# 4-PT100-B.net
KiCad netlist of a schematic drawn in EAGLE
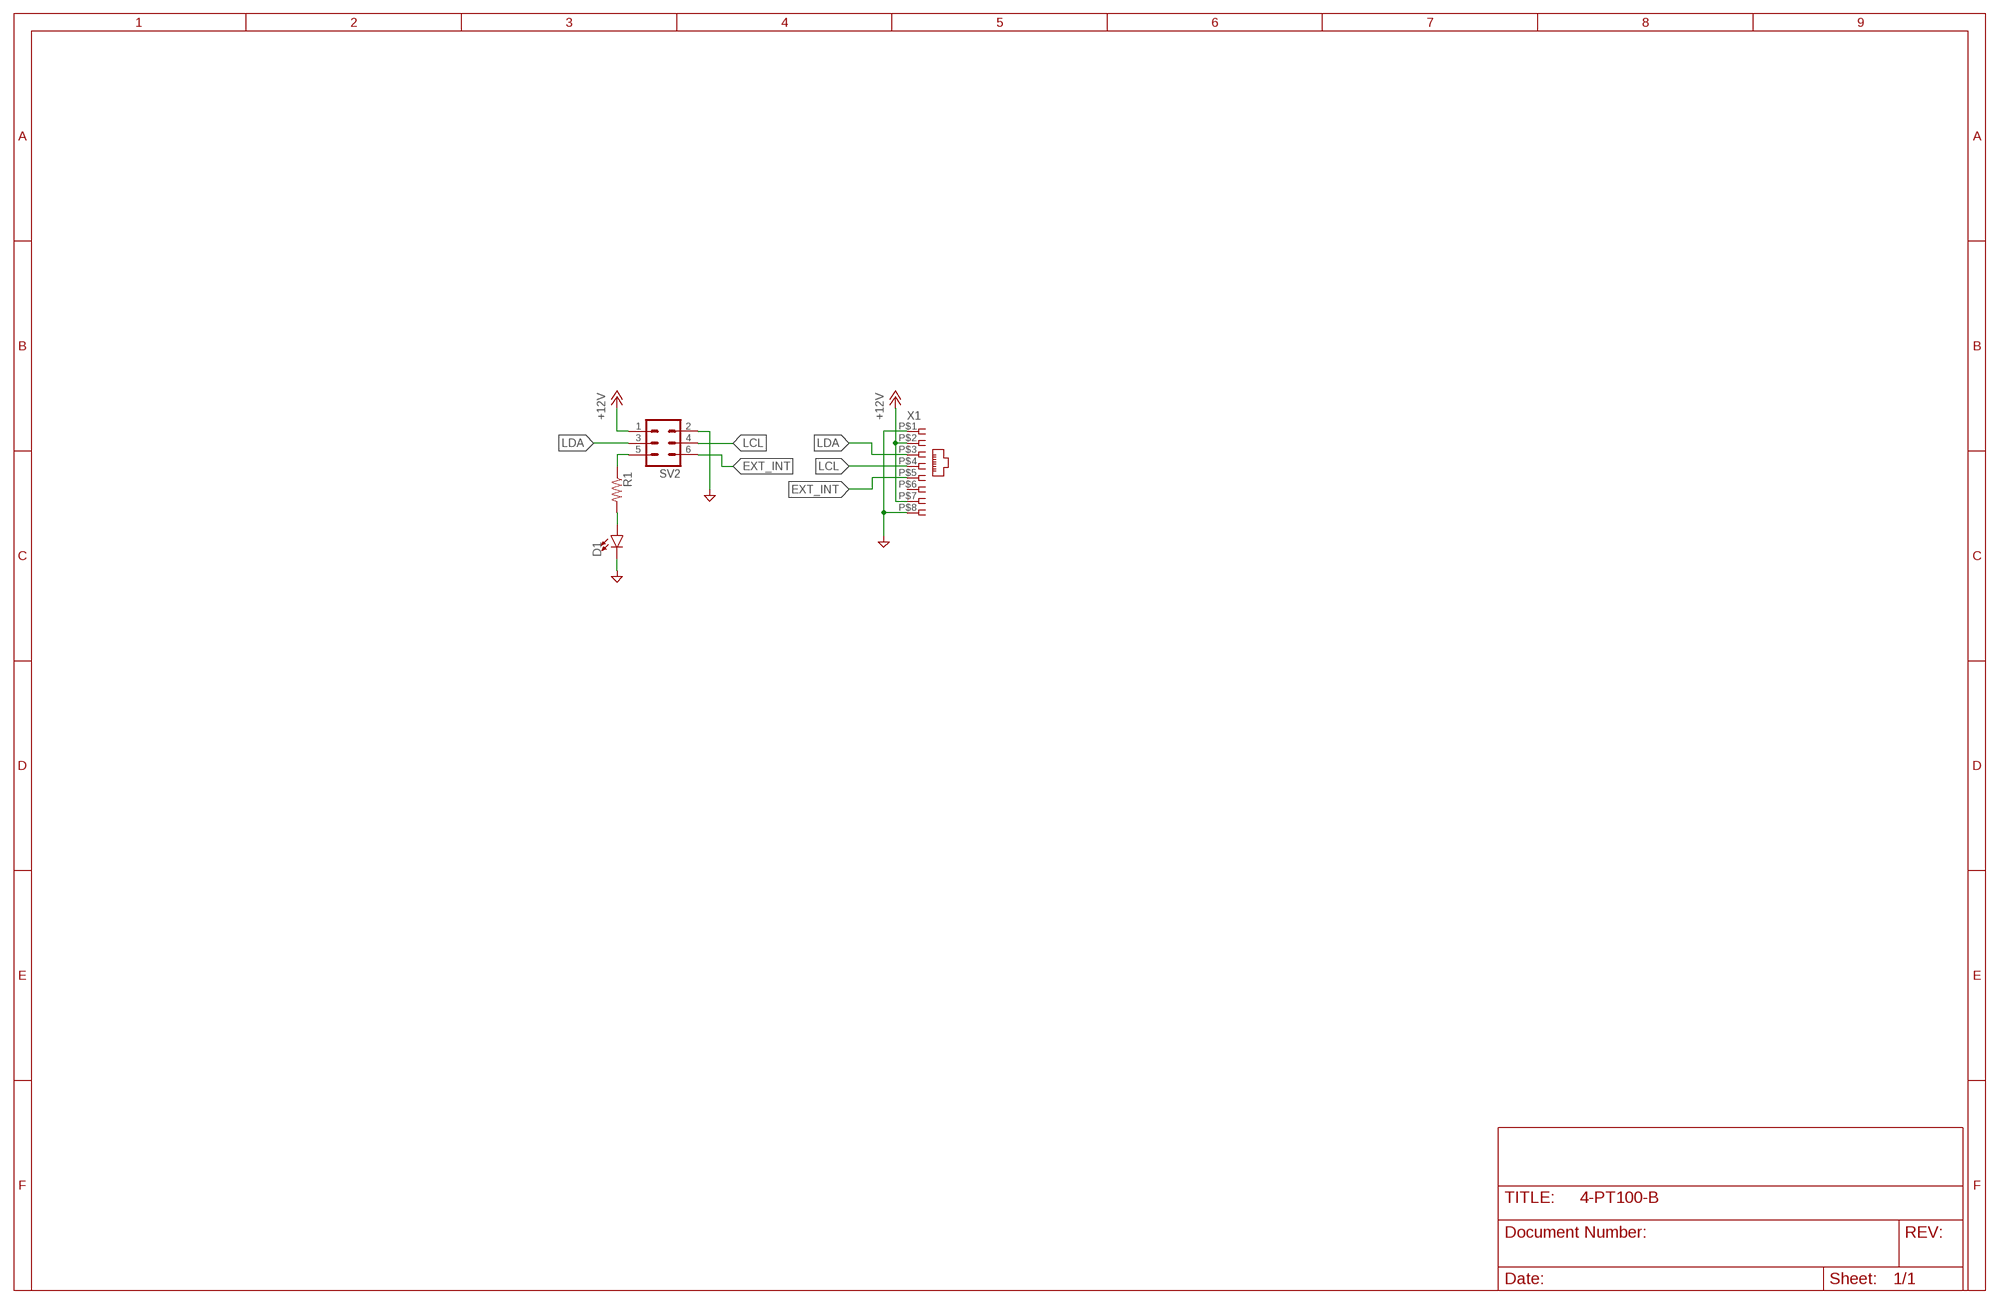
[diagram p0: schematic, sheet 1]

(export (version "E")
  (design (tool "Eeschema 10.0.6"))
  (components
    (comp (ref "D1")
      (value "LED3MM")
      (footprint "eagle-import:LED_3MM")
      (libsource (lib "eagle-import") (part "LED3MM"))
    )
    (comp (ref "R1")
      (value "R-US_R0805")
      (footprint "eagle-import:R0805")
      (libsource (lib "eagle-import") (part "R-US_R0805"))
    )
    (comp (ref "SV2")
      (value "ML6")
      (footprint "eagle-import:ML6")
      (libsource (lib "eagle-import") (part "ML6"))
    )
    (comp (ref "X1")
      (value "RJ45")
      (footprint "eagle-import:RJ45-VERT")
      (libsource (lib "eagle-import") (part "RJ45"))
    )
  )
  (nets
    (net (code "1") (name "+12V") (class "Default")
      (node (ref "SV2") (pin "1") (pinfunction "1_1") (pintype "passive"))
      (node (ref "X1") (pin "P$2") (pinfunction "2_P$2") (pintype "passive"))
      (node (ref "X1") (pin "P$7") (pinfunction "7_P$7") (pintype "passive"))
    )
    (net (code "2") (name "EXT_INT") (class "Default")
      (node (ref "SV2") (pin "6") (pinfunction "6_6") (pintype "passive"))
      (node (ref "X1") (pin "P$5") (pinfunction "5_P$5") (pintype "passive"))
    )
    (net (code "3") (name "LCL") (class "Default")
      (node (ref "SV2") (pin "4") (pinfunction "4_4") (pintype "passive"))
      (node (ref "X1") (pin "P$4") (pinfunction "4_P$4") (pintype "passive"))
    )
    (net (code "4") (name "LDA") (class "Default")
      (node (ref "SV2") (pin "3") (pinfunction "3_3") (pintype "passive"))
      (node (ref "X1") (pin "P$3") (pinfunction "3_P$3") (pintype "passive"))
    )
    (net (code "5") (name "Net-(D1-PadA)") (class "Default")
      (node (ref "D1") (pin "A") (pinfunction "A_A") (pintype "passive"))
      (node (ref "R1") (pin "2") (pinfunction "2_2") (pintype "passive"))
    )
    (net (code "6") (name "Net-(R1-Pad1)") (class "Default")
      (node (ref "R1") (pin "1") (pinfunction "1_1") (pintype "passive"))
      (node (ref "SV2") (pin "5") (pinfunction "5_5") (pintype "passive"))
    )
    (net (code "7") (name "VDG") (class "Default")
      (node (ref "D1") (pin "K") (pinfunction "C_K") (pintype "passive"))
      (node (ref "SV2") (pin "2") (pinfunction "2_2") (pintype "passive"))
      (node (ref "X1") (pin "P$1") (pinfunction "1_P$1") (pintype "passive"))
      (node (ref "X1") (pin "P$8") (pinfunction "8_P$8") (pintype "passive"))
    )
    (net (code "8") (name "unconnected-(X1-6-PadP$6)") (class "Default")
      (node (ref "X1") (pin "P$6") (pinfunction "6_P$6") (pintype "passive"))
    )
  )
)
